# buttons2.net
KiCad netlist of a schematic drawn in EAGLE
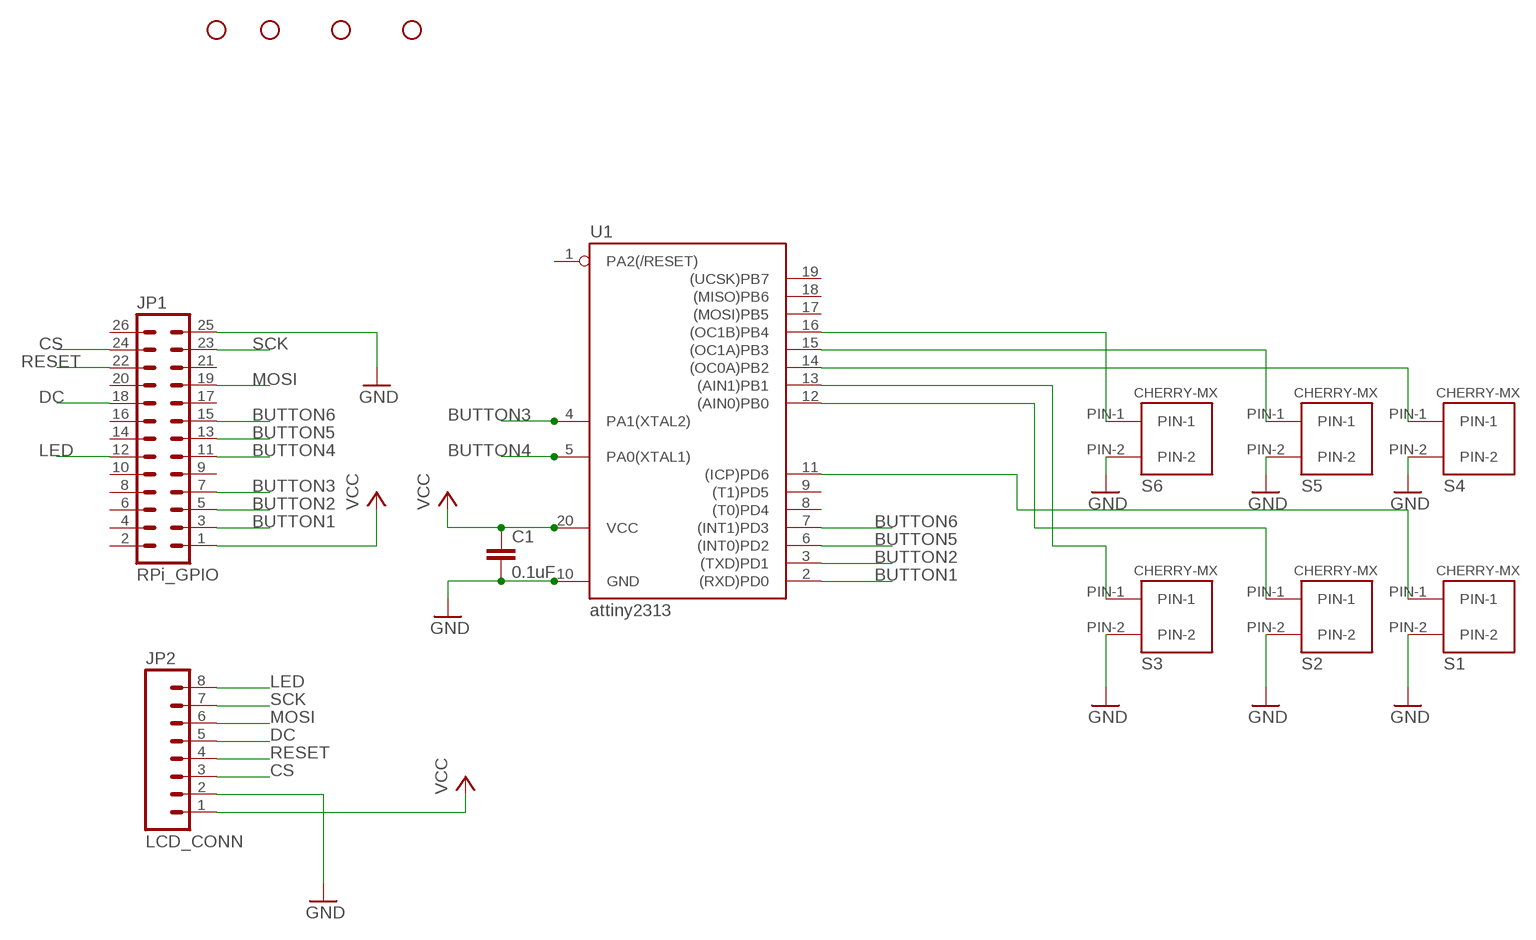
[diagram p0: schematic, sheet 1]

(export (version "E")
  (design (tool "Eeschema 10.0.6"))
  (components
    (comp (ref "C1")
      (value "0.1uF")
      (footprint "eagle-import:C2.5-2")
      (libsource (lib "eagle-import") (part "C2.5/2"))
    )
    (comp (ref "JP1")
      (value "RPi_GPIO")
      (footprint "eagle-import:ML26")
      (libsource (lib "eagle-import") (part "ML26"))
    )
    (comp (ref "JP2")
      (value "LCD_CONN")
      (footprint "eagle-import:1X08")
      (libsource (lib "eagle-import") (part "M081X08"))
    )
    (comp (ref "S1")
      (value "CHERRY-MX-I")
      (footprint "eagle-import:CHERRY-MX-I")
      (libsource (lib "eagle-import") (part "CHERRY-MX-I"))
    )
    (comp (ref "S2")
      (value "CHERRY-MX-I")
      (footprint "eagle-import:CHERRY-MX-I")
      (libsource (lib "eagle-import") (part "CHERRY-MX-I"))
    )
    (comp (ref "S3")
      (value "CHERRY-MX-I")
      (footprint "eagle-import:CHERRY-MX-I")
      (libsource (lib "eagle-import") (part "CHERRY-MX-I"))
    )
    (comp (ref "S4")
      (value "CHERRY-MX-I")
      (footprint "eagle-import:CHERRY-MX-I")
      (libsource (lib "eagle-import") (part "CHERRY-MX-I"))
    )
    (comp (ref "S5")
      (value "CHERRY-MX-I")
      (footprint "eagle-import:CHERRY-MX-I")
      (libsource (lib "eagle-import") (part "CHERRY-MX-I"))
    )
    (comp (ref "S6")
      (value "CHERRY-MX-I")
      (footprint "eagle-import:CHERRY-MX-I")
      (libsource (lib "eagle-import") (part "CHERRY-MX-I"))
    )
    (comp (ref "STANDOFF1")
      (value "STAND-OFF")
      (footprint "eagle-import:STAND-OFF")
      (libsource (lib "eagle-import") (part "STAND-OFF"))
    )
    (comp (ref "STANDOFF2")
      (value "STAND-OFF")
      (footprint "eagle-import:STAND-OFF")
      (libsource (lib "eagle-import") (part "STAND-OFF"))
    )
    (comp (ref "STANDOFF3")
      (value "STAND-OFF")
      (footprint "eagle-import:STAND-OFF")
      (libsource (lib "eagle-import") (part "STAND-OFF"))
    )
    (comp (ref "STANDOFF4")
      (value "STAND-OFF")
      (footprint "eagle-import:STAND-OFF")
      (libsource (lib "eagle-import") (part "STAND-OFF"))
    )
    (comp (ref "U1")
      (value "attiny2313")
      (footprint "eagle-import:DIL20")
      (libsource (lib "eagle-import") (part "TINY2313-P"))
    )
  )
  (nets
    (net (code "1") (name "/BUTTON1") (class "Default")
      (node (ref "JP1") (pin "3") (pinfunction "3_3") (pintype "passive"))
      (node (ref "U1") (pin "2") (pinfunction "(RXD)PD0_2") (pintype "bidirectional"))
    )
    (net (code "2") (name "/BUTTON2") (class "Default")
      (node (ref "JP1") (pin "5") (pinfunction "5_5") (pintype "passive"))
      (node (ref "U1") (pin "3") (pinfunction "(TXD)PD1_3") (pintype "bidirectional"))
    )
    (net (code "3") (name "/BUTTON3") (class "Default")
      (node (ref "JP1") (pin "7") (pinfunction "7_7") (pintype "passive"))
      (node (ref "U1") (pin "4") (pinfunction "PA1(XTAL2)_4") (pintype "bidirectional"))
    )
    (net (code "4") (name "/BUTTON4") (class "Default")
      (node (ref "JP1") (pin "11") (pinfunction "11_11") (pintype "passive"))
      (node (ref "U1") (pin "5") (pinfunction "PA0(XTAL1)_5") (pintype "bidirectional"))
    )
    (net (code "5") (name "/BUTTON5") (class "Default")
      (node (ref "JP1") (pin "13") (pinfunction "13_13") (pintype "passive"))
      (node (ref "U1") (pin "6") (pinfunction "(INT0)PD2_6") (pintype "bidirectional"))
    )
    (net (code "6") (name "/BUTTON6") (class "Default")
      (node (ref "JP1") (pin "15") (pinfunction "15_15") (pintype "passive"))
      (node (ref "U1") (pin "7") (pinfunction "(INT1)PD3_7") (pintype "bidirectional"))
    )
    (net (code "7") (name "/CS") (class "Default")
      (node (ref "JP1") (pin "24") (pinfunction "24_24") (pintype "passive"))
      (node (ref "JP2") (pin "3") (pinfunction "3_3") (pintype "passive"))
    )
    (net (code "8") (name "/DC") (class "Default")
      (node (ref "JP1") (pin "18") (pinfunction "18_18") (pintype "passive"))
      (node (ref "JP2") (pin "5") (pinfunction "5_5") (pintype "passive"))
    )
    (net (code "9") (name "/LED") (class "Default")
      (node (ref "JP1") (pin "12") (pinfunction "12_12") (pintype "passive"))
      (node (ref "JP2") (pin "8") (pinfunction "8_8") (pintype "passive"))
    )
    (net (code "10") (name "/MOSI") (class "Default")
      (node (ref "JP1") (pin "19") (pinfunction "19_19") (pintype "passive"))
      (node (ref "JP2") (pin "6") (pinfunction "6_6") (pintype "passive"))
    )
    (net (code "11") (name "/RESET") (class "Default")
      (node (ref "JP1") (pin "22") (pinfunction "22_22") (pintype "passive"))
      (node (ref "JP2") (pin "4") (pinfunction "4_4") (pintype "passive"))
    )
    (net (code "12") (name "/SCK") (class "Default")
      (node (ref "JP1") (pin "23") (pinfunction "23_23") (pintype "passive"))
      (node (ref "JP2") (pin "7") (pinfunction "7_7") (pintype "passive"))
    )
    (net (code "13") (name "GND") (class "Default")
      (node (ref "C1") (pin "2") (pinfunction "2_2") (pintype "passive"))
      (node (ref "JP1") (pin "25") (pinfunction "25_25") (pintype "passive"))
      (node (ref "JP2") (pin "2") (pinfunction "2_2") (pintype "passive"))
      (node (ref "S1") (pin "PIN-2") (pinfunction "PIN-2_PIN-2") (pintype "bidirectional"))
      (node (ref "S2") (pin "PIN-2") (pinfunction "PIN-2_PIN-2") (pintype "bidirectional"))
      (node (ref "S3") (pin "PIN-2") (pinfunction "PIN-2_PIN-2") (pintype "bidirectional"))
      (node (ref "S4") (pin "PIN-2") (pinfunction "PIN-2_PIN-2") (pintype "bidirectional"))
      (node (ref "S5") (pin "PIN-2") (pinfunction "PIN-2_PIN-2") (pintype "bidirectional"))
      (node (ref "S6") (pin "PIN-2") (pinfunction "PIN-2_PIN-2") (pintype "bidirectional"))
      (node (ref "U1") (pin "10") (pinfunction "GND_10") (pintype "power_in"))
    )
    (net (code "14") (name "Net-(U1-(AIN0)PB0)") (class "Default")
      (node (ref "S2") (pin "PIN-1") (pinfunction "PIN-1_PIN-1") (pintype "bidirectional"))
      (node (ref "U1") (pin "12") (pinfunction "(AIN0)PB0_12") (pintype "bidirectional"))
    )
    (net (code "15") (name "Net-(U1-(AIN1)PB1)") (class "Default")
      (node (ref "S3") (pin "PIN-1") (pinfunction "PIN-1_PIN-1") (pintype "bidirectional"))
      (node (ref "U1") (pin "13") (pinfunction "(AIN1)PB1_13") (pintype "bidirectional"))
    )
    (net (code "16") (name "Net-(U1-(ICP)PD6)") (class "Default")
      (node (ref "S1") (pin "PIN-1") (pinfunction "PIN-1_PIN-1") (pintype "bidirectional"))
      (node (ref "U1") (pin "11") (pinfunction "(ICP)PD6_11") (pintype "bidirectional"))
    )
    (net (code "17") (name "Net-(U1-(OC0A)PB2)") (class "Default")
      (node (ref "S4") (pin "PIN-1") (pinfunction "PIN-1_PIN-1") (pintype "bidirectional"))
      (node (ref "U1") (pin "14") (pinfunction "(OC0A)PB2_14") (pintype "bidirectional"))
    )
    (net (code "18") (name "Net-(U1-(OC1A)PB3)") (class "Default")
      (node (ref "S5") (pin "PIN-1") (pinfunction "PIN-1_PIN-1") (pintype "bidirectional"))
      (node (ref "U1") (pin "15") (pinfunction "(OC1A)PB3_15") (pintype "bidirectional"))
    )
    (net (code "19") (name "Net-(U1-(OC1B)PB4)") (class "Default")
      (node (ref "S6") (pin "PIN-1") (pinfunction "PIN-1_PIN-1") (pintype "bidirectional"))
      (node (ref "U1") (pin "16") (pinfunction "(OC1B)PB4_16") (pintype "bidirectional"))
    )
    (net (code "20") (name "VCC") (class "Default")
      (node (ref "C1") (pin "1") (pinfunction "1_1") (pintype "passive"))
      (node (ref "JP1") (pin "1") (pinfunction "1_1") (pintype "passive"))
      (node (ref "JP2") (pin "1") (pinfunction "1_1") (pintype "passive"))
      (node (ref "U1") (pin "20") (pinfunction "VCC_20") (pintype "power_in"))
    )
    (net (code "21") (name "unconnected-(JP1-Pad2)") (class "Default")
      (node (ref "JP1") (pin "2") (pinfunction "2_2") (pintype "passive"))
    )
    (net (code "22") (name "unconnected-(JP1-Pad4)") (class "Default")
      (node (ref "JP1") (pin "4") (pinfunction "4_4") (pintype "passive"))
    )
    (net (code "23") (name "unconnected-(JP1-Pad6)") (class "Default")
      (node (ref "JP1") (pin "6") (pinfunction "6_6") (pintype "passive"))
    )
    (net (code "24") (name "unconnected-(JP1-Pad8)") (class "Default")
      (node (ref "JP1") (pin "8") (pinfunction "8_8") (pintype "passive"))
    )
    (net (code "25") (name "unconnected-(JP1-Pad9)") (class "Default")
      (node (ref "JP1") (pin "9") (pinfunction "9_9") (pintype "passive"))
    )
    (net (code "26") (name "unconnected-(JP1-Pad10)") (class "Default")
      (node (ref "JP1") (pin "10") (pinfunction "10_10") (pintype "passive"))
    )
    (net (code "27") (name "unconnected-(JP1-Pad14)") (class "Default")
      (node (ref "JP1") (pin "14") (pinfunction "14_14") (pintype "passive"))
    )
    (net (code "28") (name "unconnected-(JP1-Pad16)") (class "Default")
      (node (ref "JP1") (pin "16") (pinfunction "16_16") (pintype "passive"))
    )
    (net (code "29") (name "unconnected-(JP1-Pad17)") (class "Default")
      (node (ref "JP1") (pin "17") (pinfunction "17_17") (pintype "passive"))
    )
    (net (code "30") (name "unconnected-(JP1-Pad20)") (class "Default")
      (node (ref "JP1") (pin "20") (pinfunction "20_20") (pintype "passive"))
    )
    (net (code "31") (name "unconnected-(JP1-Pad21)") (class "Default")
      (node (ref "JP1") (pin "21") (pinfunction "21_21") (pintype "passive"))
    )
    (net (code "32") (name "unconnected-(JP1-Pad26)") (class "Default")
      (node (ref "JP1") (pin "26") (pinfunction "26_26") (pintype "passive"))
    )
    (net (code "33") (name "unconnected-(U1-(MISO)PB6-Pad18)") (class "Default")
      (node (ref "U1") (pin "18") (pinfunction "(MISO)PB6_18") (pintype "bidirectional"))
    )
    (net (code "34") (name "unconnected-(U1-(MOSI)PB5-Pad17)") (class "Default")
      (node (ref "U1") (pin "17") (pinfunction "(MOSI)PB5_17") (pintype "bidirectional"))
    )
    (net (code "35") (name "unconnected-(U1-(T0)PD4-Pad8)") (class "Default")
      (node (ref "U1") (pin "8") (pinfunction "(T0)PD4_8") (pintype "bidirectional"))
    )
    (net (code "36") (name "unconnected-(U1-(T1)PD5-Pad9)") (class "Default")
      (node (ref "U1") (pin "9") (pinfunction "(T1)PD5_9") (pintype "bidirectional"))
    )
    (net (code "37") (name "unconnected-(U1-(UCSK)PB7-Pad19)") (class "Default")
      (node (ref "U1") (pin "19") (pinfunction "(UCSK)PB7_19") (pintype "bidirectional"))
    )
    (net (code "38") (name "unconnected-(U1-PA2({slash}RESET)-Pad1)") (class "Default")
      (node (ref "U1") (pin "1") (pinfunction "PA2(/RESET)_1") (pintype "input"))
    )
  )
)
